# Power.net
KiCad netlist of a schematic drawn in Altium Designer
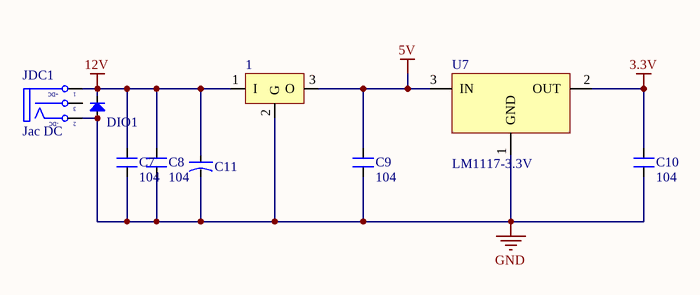
[diagram p0: Power.SchDoc]

(export (version "E")
  (design (tool "Eeschema 10.0.6"))
  (components
    (comp (ref "1")
      (value "LM78xx")
      (footprint "TO252-123")
      (description "Positive Voltage Regulator")
      (fields (field (name "PUBLISHER") "Altium Limited"))
      (libsource (lib "LIBRARY") (part "LM78xx"))
    )
    (comp (ref "C7")
      (value "104")
      (footprint "SM-CAP-0805")
      (fields (field (name "DESIGNED BY") "VanDungEvn"))
      (libsource (lib "electronicvn-library1") (part "CN"))
    )
    (comp (ref "C8")
      (value "104")
      (footprint "SM-CAP-0805")
      (fields (field (name "DESIGNED BY") "VanDungEvn"))
      (libsource (lib "electronicvn-library1") (part "CN"))
    )
    (comp (ref "C9")
      (value "104")
      (footprint "SM-CAP-0805")
      (fields (field (name "DESIGNED BY") "VanDungEvn"))
      (libsource (lib "electronicvn-library1") (part "CN"))
    )
    (comp (ref "C10")
      (value "104")
      (footprint "SM-CAP-0805")
      (fields (field (name "DESIGNED BY") "VanDungEvn"))
      (libsource (lib "electronicvn-library1") (part "CN"))
    )
    (comp (ref "C11")
      (value "CN-ALU-SMD")
      (footprint "CAP-ALU-SMD-4.5x5x1.4")
      (description "Polarized Capacitor (Axial)")
      (fields (field (name "PUBLISHER") "Altium Limited"))
      (libsource (lib "LIBTanCN") (part "CN-ALU-SMD"))
    )
    (comp (ref "DIO1")
      (value "Diode SMD")
      (footprint "DIO-SMD-106")
      (description "Default Diode")
      (fields (field (name "PUBLISHER") "Altium Limited"))
      (libsource (lib "LIBRARY") (part "Diode SMD"))
    )
    (comp (ref "JDC1")
      (value "Jac DC")
      (footprint "DC3")
      (description "Jac DC input")
      (libsource (lib "LIBRARY") (part "DCIN"))
    )
    (comp (ref "U7")
      (value "LM1117-3.3V")
      (footprint "SOT223")
      (description "800mA Low-Dropout Linear Regulator")
      (fields (field (name "CREATOR") "Nguyen Ba Bien"))
      (libsource (lib "LIBRARY") (part "LM1117"))
    )
  )
  (nets
    (net (code "1") (name "3.3V") (class "Default")
      (node (ref "C10") (pin "2") (pinfunction "2_2") (pintype "passive"))
      (node (ref "U7") (pin "2") (pinfunction "OUT_2") (pintype "passive"))
    )
    (net (code "2") (name "5V") (class "Default")
      (node (ref "1") (pin "3") (pinfunction "O_3") (pintype "power_in"))
      (node (ref "C9") (pin "2") (pinfunction "2_2") (pintype "passive"))
      (node (ref "U7") (pin "3") (pinfunction "IN_3") (pintype "passive"))
    )
    (net (code "3") (name "12V") (class "Default")
      (node (ref "1") (pin "1") (pinfunction "I_1") (pintype "power_in"))
      (node (ref "C11") (pin "1") (pinfunction "1_1") (pintype "passive"))
      (node (ref "C7") (pin "2") (pinfunction "2_2") (pintype "passive"))
      (node (ref "C8") (pin "2") (pinfunction "2_2") (pintype "passive"))
      (node (ref "DIO1") (pin "2") (pinfunction "K_2") (pintype "passive"))
      (node (ref "JDC1") (pin "1") (pinfunction "T_1") (pintype "passive"))
    )
    (net (code "4") (name "GND") (class "Default")
      (node (ref "1") (pin "2") (pinfunction "G_2") (pintype "power_in"))
      (node (ref "C10") (pin "1") (pinfunction "1_1") (pintype "passive"))
      (node (ref "C11") (pin "2") (pinfunction "2_2") (pintype "passive"))
      (node (ref "C7") (pin "1") (pinfunction "1_1") (pintype "passive"))
      (node (ref "C8") (pin "1") (pinfunction "1_1") (pintype "passive"))
      (node (ref "C9") (pin "1") (pinfunction "1_1") (pintype "passive"))
      (node (ref "DIO1") (pin "1") (pinfunction "A_1") (pintype "passive"))
      (node (ref "JDC1") (pin "2") (pinfunction "TN_2") (pintype "passive"))
      (node (ref "U7") (pin "1") (pinfunction "GND_1") (pintype "passive"))
    )
    (net (code "5") (name "unconnected-(JDC1-S-Pad3)") (class "Default")
      (node (ref "JDC1") (pin "3") (pinfunction "S_3") (pintype "power_in"))
    )
  )
)
